# breakout.net
KiCad netlist of a schematic drawn in EAGLE
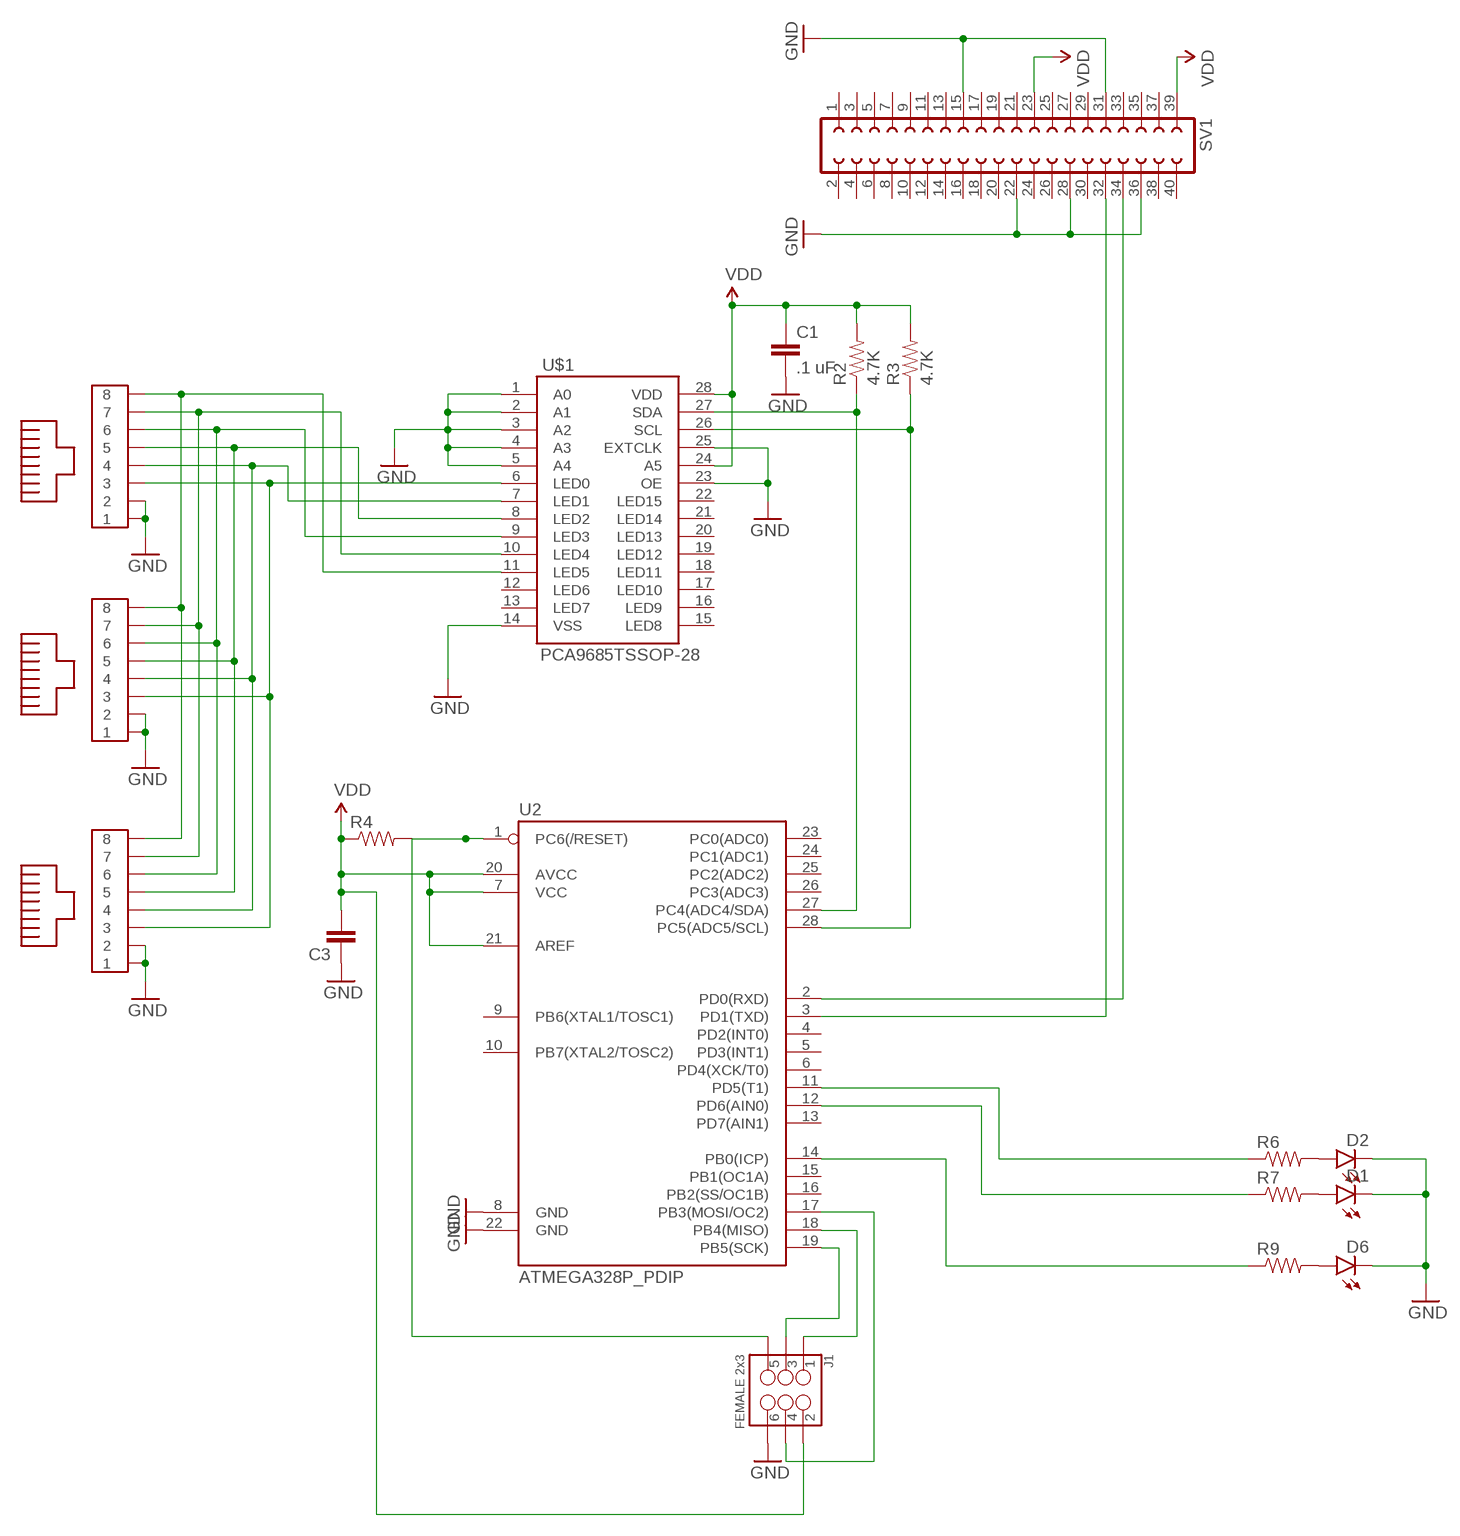
[diagram p0: schematic, sheet 1]

(export (version "E")
  (design (tool "Eeschema 10.0.6"))
  (components
    (comp (ref "C1")
      (value ".1 uF")
      (footprint "eagle-import:1206")
      (libsource (lib "eagle-import") (part "CAP1206"))
    )
    (comp (ref "C3")
      (value "CAP1206")
      (footprint "eagle-import:1206")
      (libsource (lib "eagle-import") (part "CAP1206"))
    )
    (comp (ref "D1")
      (value "LED0603")
      (footprint "eagle-import:LED-0603")
      (libsource (lib "eagle-import") (part "LED0603"))
    )
    (comp (ref "D2")
      (value "LED0603")
      (footprint "eagle-import:LED-0603")
      (libsource (lib "eagle-import") (part "LED0603"))
    )
    (comp (ref "D6")
      (value "LED0603")
      (footprint "eagle-import:LED-0603")
      (libsource (lib "eagle-import") (part "LED0603"))
    )
    (comp (ref "J1")
      (value "FEMALE 2x3")
      (footprint "eagle-import:2X3")
      (libsource (lib "eagle-import") (part "M03X2FEMALE"))
    )
    (comp (ref "R2")
      (value "4.7K")
      (footprint "eagle-import:1206")
      (libsource (lib "eagle-import") (part "RESISTOR1206"))
    )
    (comp (ref "R3")
      (value "4.7K")
      (footprint "eagle-import:1206")
      (libsource (lib "eagle-import") (part "RESISTOR1206"))
    )
    (comp (ref "R4")
      (value "RESISTOR1206")
      (footprint "eagle-import:1206")
      (libsource (lib "eagle-import") (part "RESISTOR1206"))
    )
    (comp (ref "R6")
      (value "RESISTOR1206")
      (footprint "eagle-import:1206")
      (libsource (lib "eagle-import") (part "RESISTOR1206"))
    )
    (comp (ref "R7")
      (value "RESISTOR1206")
      (footprint "eagle-import:1206")
      (libsource (lib "eagle-import") (part "RESISTOR1206"))
    )
    (comp (ref "R9")
      (value "RESISTOR1206")
      (footprint "eagle-import:1206")
      (libsource (lib "eagle-import") (part "RESISTOR1206"))
    )
    (comp (ref "SV1")
      (value "FE20-2")
      (footprint "eagle-import:FE20-2")
      (libsource (lib "eagle-import") (part "FE20-2"))
    )
    (comp (ref "U$1")
      (value "PCA9685TSSOP-28")
      (footprint "eagle-import:TSSOP28")
      (libsource (lib "eagle-import") (part "PCA9685TSSOP-28"))
    )
    (comp (ref "U$2")
      (value "MOLEX-RJ45-SMT")
      (footprint "eagle-import:MOLEX-RJ45-SMT")
      (libsource (lib "eagle-import") (part "MOLEX-RJ45-SMT"))
    )
    (comp (ref "U$3")
      (value "MOLEX-RJ45-SMT")
      (footprint "eagle-import:MOLEX-RJ45-SMT")
      (libsource (lib "eagle-import") (part "MOLEX-RJ45-SMT"))
    )
    (comp (ref "U$4")
      (value "MOLEX-RJ45-SMT")
      (footprint "eagle-import:MOLEX-RJ45-SMT")
      (libsource (lib "eagle-import") (part "MOLEX-RJ45-SMT"))
    )
    (comp (ref "U2")
      (value "ATMEGA328P_PDIP")
      (footprint "eagle-import:DIL28-3")
      (libsource (lib "eagle-import") (part "ATMEGA328P_PDIP"))
    )
  )
  (nets
    (net (code "1") (name "GND") (class "Default")
      (node (ref "C1") (pin "2") (pinfunction "2_2") (pintype "passive"))
      (node (ref "C3") (pin "1") (pinfunction "1_1") (pintype "passive"))
      (node (ref "D1") (pin "C") (pinfunction "C_C") (pintype "passive"))
      (node (ref "D2") (pin "C") (pinfunction "C_C") (pintype "passive"))
      (node (ref "D6") (pin "C") (pinfunction "C_C") (pintype "passive"))
      (node (ref "J1") (pin "6") (pinfunction "6_6") (pintype "bidirectional"))
      (node (ref "SV1") (pin "15") (pinfunction "15_15") (pintype "passive"))
      (node (ref "SV1") (pin "22") (pinfunction "22_22") (pintype "passive"))
      (node (ref "SV1") (pin "28") (pinfunction "28_28") (pintype "passive"))
      (node (ref "SV1") (pin "31") (pinfunction "31_31") (pintype "passive"))
      (node (ref "SV1") (pin "36") (pinfunction "36_36") (pintype "passive"))
      (node (ref "U$1") (pin "1") (pinfunction "A0_1") (pintype "bidirectional"))
      (node (ref "U$1") (pin "14") (pinfunction "VSS_14") (pintype "bidirectional"))
      (node (ref "U$1") (pin "2") (pinfunction "A1_2") (pintype "bidirectional"))
      (node (ref "U$1") (pin "23") (pinfunction "OE_23") (pintype "bidirectional"))
      (node (ref "U$1") (pin "25") (pinfunction "EXTCLK_25") (pintype "bidirectional"))
      (node (ref "U$1") (pin "3") (pinfunction "A2_3") (pintype "bidirectional"))
      (node (ref "U$1") (pin "4") (pinfunction "A3_4") (pintype "bidirectional"))
      (node (ref "U$1") (pin "5") (pinfunction "A4_5") (pintype "bidirectional"))
      (node (ref "U$2") (pin "1") (pinfunction "1_1") (pintype "bidirectional"))
      (node (ref "U$2") (pin "2") (pinfunction "2_2") (pintype "bidirectional"))
      (node (ref "U$3") (pin "1") (pinfunction "1_1") (pintype "bidirectional"))
      (node (ref "U$3") (pin "2") (pinfunction "2_2") (pintype "bidirectional"))
      (node (ref "U$4") (pin "1") (pinfunction "1_1") (pintype "bidirectional"))
      (node (ref "U$4") (pin "2") (pinfunction "2_2") (pintype "bidirectional"))
      (node (ref "U2") (pin "22") (pinfunction "GND_22") (pintype "bidirectional"))
      (node (ref "U2") (pin "8") (pinfunction "GND_8") (pintype "bidirectional"))
    )
    (net (code "2") (name "Net-(D1-PadA)") (class "Default")
      (node (ref "D1") (pin "A") (pinfunction "A_A") (pintype "passive"))
      (node (ref "R7") (pin "2") (pinfunction "2_2") (pintype "passive"))
    )
    (net (code "3") (name "Net-(D2-PadA)") (class "Default")
      (node (ref "D2") (pin "A") (pinfunction "A_A") (pintype "passive"))
      (node (ref "R6") (pin "2") (pinfunction "2_2") (pintype "passive"))
    )
    (net (code "4") (name "Net-(D6-PadA)") (class "Default")
      (node (ref "D6") (pin "A") (pinfunction "A_A") (pintype "passive"))
      (node (ref "R9") (pin "2") (pinfunction "2_2") (pintype "passive"))
    )
    (net (code "5") (name "Net-(U$1-LED0)") (class "Default")
      (node (ref "U$1") (pin "6") (pinfunction "LED0_6") (pintype "bidirectional"))
      (node (ref "U$2") (pin "3") (pinfunction "3_3") (pintype "bidirectional"))
      (node (ref "U$3") (pin "3") (pinfunction "3_3") (pintype "bidirectional"))
      (node (ref "U$4") (pin "3") (pinfunction "3_3") (pintype "bidirectional"))
    )
    (net (code "6") (name "Net-(U$1-LED1)") (class "Default")
      (node (ref "U$1") (pin "7") (pinfunction "LED1_7") (pintype "bidirectional"))
      (node (ref "U$2") (pin "4") (pinfunction "4_4") (pintype "bidirectional"))
      (node (ref "U$3") (pin "4") (pinfunction "4_4") (pintype "bidirectional"))
      (node (ref "U$4") (pin "4") (pinfunction "4_4") (pintype "bidirectional"))
    )
    (net (code "7") (name "Net-(U$1-LED2)") (class "Default")
      (node (ref "U$1") (pin "8") (pinfunction "LED2_8") (pintype "bidirectional"))
      (node (ref "U$2") (pin "5") (pinfunction "5_5") (pintype "bidirectional"))
      (node (ref "U$3") (pin "5") (pinfunction "5_5") (pintype "bidirectional"))
      (node (ref "U$4") (pin "5") (pinfunction "5_5") (pintype "bidirectional"))
    )
    (net (code "8") (name "Net-(U$1-LED3)") (class "Default")
      (node (ref "U$1") (pin "9") (pinfunction "LED3_9") (pintype "bidirectional"))
      (node (ref "U$2") (pin "6") (pinfunction "6_6") (pintype "bidirectional"))
      (node (ref "U$3") (pin "6") (pinfunction "6_6") (pintype "bidirectional"))
      (node (ref "U$4") (pin "6") (pinfunction "6_6") (pintype "bidirectional"))
    )
    (net (code "9") (name "Net-(U$1-LED4)") (class "Default")
      (node (ref "U$1") (pin "10") (pinfunction "LED4_10") (pintype "bidirectional"))
      (node (ref "U$2") (pin "7") (pinfunction "7_7") (pintype "bidirectional"))
      (node (ref "U$3") (pin "7") (pinfunction "7_7") (pintype "bidirectional"))
      (node (ref "U$4") (pin "7") (pinfunction "7_7") (pintype "bidirectional"))
    )
    (net (code "10") (name "Net-(U$1-LED5)") (class "Default")
      (node (ref "U$1") (pin "11") (pinfunction "LED5_11") (pintype "bidirectional"))
      (node (ref "U$2") (pin "8") (pinfunction "8_8") (pintype "bidirectional"))
      (node (ref "U$3") (pin "8") (pinfunction "8_8") (pintype "bidirectional"))
      (node (ref "U$4") (pin "8") (pinfunction "8_8") (pintype "bidirectional"))
    )
    (net (code "11") (name "Net-(U$1-SCL)") (class "Default")
      (node (ref "R3") (pin "1") (pinfunction "1_1") (pintype "passive"))
      (node (ref "U$1") (pin "26") (pinfunction "SCL_26") (pintype "bidirectional"))
      (node (ref "U2") (pin "28") (pinfunction "PC5(ADC5/SCL)_28") (pintype "bidirectional"))
    )
    (net (code "12") (name "Net-(U$1-SDA)") (class "Default")
      (node (ref "R2") (pin "1") (pinfunction "1_1") (pintype "passive"))
      (node (ref "U$1") (pin "27") (pinfunction "SDA_27") (pintype "bidirectional"))
      (node (ref "U2") (pin "27") (pinfunction "PC4(ADC4/SDA)_27") (pintype "bidirectional"))
    )
    (net (code "13") (name "Net-(U2-PB0(ICP))") (class "Default")
      (node (ref "R9") (pin "1") (pinfunction "1_1") (pintype "passive"))
      (node (ref "U2") (pin "14") (pinfunction "PB0(ICP)_14") (pintype "bidirectional"))
    )
    (net (code "14") (name "Net-(U2-PB3(MOSI{slash}OC2))") (class "Default")
      (node (ref "J1") (pin "4") (pinfunction "4_4") (pintype "bidirectional"))
      (node (ref "U2") (pin "17") (pinfunction "PB3(MOSI/OC2)_17") (pintype "bidirectional"))
    )
    (net (code "15") (name "Net-(U2-PB4(MISO))") (class "Default")
      (node (ref "J1") (pin "1") (pinfunction "1_1") (pintype "bidirectional"))
      (node (ref "U2") (pin "18") (pinfunction "PB4(MISO)_18") (pintype "bidirectional"))
    )
    (net (code "16") (name "Net-(U2-PB5(SCK))") (class "Default")
      (node (ref "J1") (pin "3") (pinfunction "3_3") (pintype "bidirectional"))
      (node (ref "U2") (pin "19") (pinfunction "PB5(SCK)_19") (pintype "bidirectional"))
    )
    (net (code "17") (name "Net-(U2-PC6({slash}RESET))") (class "Default")
      (node (ref "J1") (pin "5") (pinfunction "5_5") (pintype "bidirectional"))
      (node (ref "R4") (pin "2") (pinfunction "2_2") (pintype "passive"))
      (node (ref "U2") (pin "1") (pinfunction "PC6(/RESET)_1") (pintype "bidirectional"))
    )
    (net (code "18") (name "Net-(U2-PD0(RXD))") (class "Default")
      (node (ref "SV1") (pin "34") (pinfunction "34_34") (pintype "passive"))
      (node (ref "U2") (pin "2") (pinfunction "PD0(RXD)_2") (pintype "bidirectional"))
    )
    (net (code "19") (name "Net-(U2-PD1(TXD))") (class "Default")
      (node (ref "SV1") (pin "32") (pinfunction "32_32") (pintype "passive"))
      (node (ref "U2") (pin "3") (pinfunction "PD1(TXD)_3") (pintype "bidirectional"))
    )
    (net (code "20") (name "Net-(U2-PD5(T1))") (class "Default")
      (node (ref "R6") (pin "1") (pinfunction "1_1") (pintype "passive"))
      (node (ref "U2") (pin "11") (pinfunction "PD5(T1)_11") (pintype "bidirectional"))
    )
    (net (code "21") (name "Net-(U2-PD6(AIN0))") (class "Default")
      (node (ref "R7") (pin "1") (pinfunction "1_1") (pintype "passive"))
      (node (ref "U2") (pin "12") (pinfunction "PD6(AIN0)_12") (pintype "bidirectional"))
    )
    (net (code "22") (name "VDD") (class "Default")
      (node (ref "C1") (pin "1") (pinfunction "1_1") (pintype "passive"))
      (node (ref "C3") (pin "2") (pinfunction "2_2") (pintype "passive"))
      (node (ref "J1") (pin "2") (pinfunction "2_2") (pintype "bidirectional"))
      (node (ref "R2") (pin "2") (pinfunction "2_2") (pintype "passive"))
      (node (ref "R3") (pin "2") (pinfunction "2_2") (pintype "passive"))
      (node (ref "R4") (pin "1") (pinfunction "1_1") (pintype "passive"))
      (node (ref "SV1") (pin "23") (pinfunction "23_23") (pintype "passive"))
      (node (ref "SV1") (pin "39") (pinfunction "39_39") (pintype "passive"))
      (node (ref "U$1") (pin "24") (pinfunction "A5_24") (pintype "bidirectional"))
      (node (ref "U$1") (pin "28") (pinfunction "VDD_28") (pintype "bidirectional"))
      (node (ref "U2") (pin "20") (pinfunction "AVCC_20") (pintype "bidirectional"))
      (node (ref "U2") (pin "21") (pinfunction "AREF_21") (pintype "bidirectional"))
      (node (ref "U2") (pin "7") (pinfunction "VCC_7") (pintype "bidirectional"))
    )
    (net (code "23") (name "unconnected-(SV1-Pad1)") (class "Default")
      (node (ref "SV1") (pin "1") (pinfunction "1_1") (pintype "passive"))
    )
    (net (code "24") (name "unconnected-(SV1-Pad2)") (class "Default")
      (node (ref "SV1") (pin "2") (pinfunction "2_2") (pintype "passive"))
    )
    (net (code "25") (name "unconnected-(SV1-Pad3)") (class "Default")
      (node (ref "SV1") (pin "3") (pinfunction "3_3") (pintype "passive"))
    )
    (net (code "26") (name "unconnected-(SV1-Pad4)") (class "Default")
      (node (ref "SV1") (pin "4") (pinfunction "4_4") (pintype "passive"))
    )
    (net (code "27") (name "unconnected-(SV1-Pad5)") (class "Default")
      (node (ref "SV1") (pin "5") (pinfunction "5_5") (pintype "passive"))
    )
    (net (code "28") (name "unconnected-(SV1-Pad6)") (class "Default")
      (node (ref "SV1") (pin "6") (pinfunction "6_6") (pintype "passive"))
    )
    (net (code "29") (name "unconnected-(SV1-Pad7)") (class "Default")
      (node (ref "SV1") (pin "7") (pinfunction "7_7") (pintype "passive"))
    )
    (net (code "30") (name "unconnected-(SV1-Pad8)") (class "Default")
      (node (ref "SV1") (pin "8") (pinfunction "8_8") (pintype "passive"))
    )
    (net (code "31") (name "unconnected-(SV1-Pad9)") (class "Default")
      (node (ref "SV1") (pin "9") (pinfunction "9_9") (pintype "passive"))
    )
    (net (code "32") (name "unconnected-(SV1-Pad10)") (class "Default")
      (node (ref "SV1") (pin "10") (pinfunction "10_10") (pintype "passive"))
    )
    (net (code "33") (name "unconnected-(SV1-Pad11)") (class "Default")
      (node (ref "SV1") (pin "11") (pinfunction "11_11") (pintype "passive"))
    )
    (net (code "34") (name "unconnected-(SV1-Pad12)") (class "Default")
      (node (ref "SV1") (pin "12") (pinfunction "12_12") (pintype "passive"))
    )
    (net (code "35") (name "unconnected-(SV1-Pad13)") (class "Default")
      (node (ref "SV1") (pin "13") (pinfunction "13_13") (pintype "passive"))
    )
    (net (code "36") (name "unconnected-(SV1-Pad14)") (class "Default")
      (node (ref "SV1") (pin "14") (pinfunction "14_14") (pintype "passive"))
    )
    (net (code "37") (name "unconnected-(SV1-Pad16)") (class "Default")
      (node (ref "SV1") (pin "16") (pinfunction "16_16") (pintype "passive"))
    )
    (net (code "38") (name "unconnected-(SV1-Pad17)") (class "Default")
      (node (ref "SV1") (pin "17") (pinfunction "17_17") (pintype "passive"))
    )
    (net (code "39") (name "unconnected-(SV1-Pad18)") (class "Default")
      (node (ref "SV1") (pin "18") (pinfunction "18_18") (pintype "passive"))
    )
    (net (code "40") (name "unconnected-(SV1-Pad19)") (class "Default")
      (node (ref "SV1") (pin "19") (pinfunction "19_19") (pintype "passive"))
    )
    (net (code "41") (name "unconnected-(SV1-Pad20)") (class "Default")
      (node (ref "SV1") (pin "20") (pinfunction "20_20") (pintype "passive"))
    )
    (net (code "42") (name "unconnected-(SV1-Pad21)") (class "Default")
      (node (ref "SV1") (pin "21") (pinfunction "21_21") (pintype "passive"))
    )
    (net (code "43") (name "unconnected-(SV1-Pad24)") (class "Default")
      (node (ref "SV1") (pin "24") (pinfunction "24_24") (pintype "passive"))
    )
    (net (code "44") (name "unconnected-(SV1-Pad25)") (class "Default")
      (node (ref "SV1") (pin "25") (pinfunction "25_25") (pintype "passive"))
    )
    (net (code "45") (name "unconnected-(SV1-Pad26)") (class "Default")
      (node (ref "SV1") (pin "26") (pinfunction "26_26") (pintype "passive"))
    )
    (net (code "46") (name "unconnected-(SV1-Pad27)") (class "Default")
      (node (ref "SV1") (pin "27") (pinfunction "27_27") (pintype "passive"))
    )
    (net (code "47") (name "unconnected-(SV1-Pad29)") (class "Default")
      (node (ref "SV1") (pin "29") (pinfunction "29_29") (pintype "passive"))
    )
    (net (code "48") (name "unconnected-(SV1-Pad30)") (class "Default")
      (node (ref "SV1") (pin "30") (pinfunction "30_30") (pintype "passive"))
    )
    (net (code "49") (name "unconnected-(SV1-Pad33)") (class "Default")
      (node (ref "SV1") (pin "33") (pinfunction "33_33") (pintype "passive"))
    )
    (net (code "50") (name "unconnected-(SV1-Pad35)") (class "Default")
      (node (ref "SV1") (pin "35") (pinfunction "35_35") (pintype "passive"))
    )
    (net (code "51") (name "unconnected-(SV1-Pad37)") (class "Default")
      (node (ref "SV1") (pin "37") (pinfunction "37_37") (pintype "passive"))
    )
    (net (code "52") (name "unconnected-(SV1-Pad38)") (class "Default")
      (node (ref "SV1") (pin "38") (pinfunction "38_38") (pintype "passive"))
    )
    (net (code "53") (name "unconnected-(SV1-Pad40)") (class "Default")
      (node (ref "SV1") (pin "40") (pinfunction "40_40") (pintype "passive"))
    )
    (net (code "54") (name "unconnected-(U$1-LED6-Pad12)") (class "Default")
      (node (ref "U$1") (pin "12") (pinfunction "LED6_12") (pintype "bidirectional"))
    )
    (net (code "55") (name "unconnected-(U$1-LED7-Pad13)") (class "Default")
      (node (ref "U$1") (pin "13") (pinfunction "LED7_13") (pintype "bidirectional"))
    )
    (net (code "56") (name "unconnected-(U$1-LED8-Pad15)") (class "Default")
      (node (ref "U$1") (pin "15") (pinfunction "LED8_15") (pintype "bidirectional"))
    )
    (net (code "57") (name "unconnected-(U$1-LED9-Pad16)") (class "Default")
      (node (ref "U$1") (pin "16") (pinfunction "LED9_16") (pintype "bidirectional"))
    )
    (net (code "58") (name "unconnected-(U$1-LED10-Pad17)") (class "Default")
      (node (ref "U$1") (pin "17") (pinfunction "LED10_17") (pintype "bidirectional"))
    )
    (net (code "59") (name "unconnected-(U$1-LED11-Pad18)") (class "Default")
      (node (ref "U$1") (pin "18") (pinfunction "LED11_18") (pintype "bidirectional"))
    )
    (net (code "60") (name "unconnected-(U$1-LED12-Pad19)") (class "Default")
      (node (ref "U$1") (pin "19") (pinfunction "LED12_19") (pintype "bidirectional"))
    )
    (net (code "61") (name "unconnected-(U$1-LED13-Pad20)") (class "Default")
      (node (ref "U$1") (pin "20") (pinfunction "LED13_20") (pintype "bidirectional"))
    )
    (net (code "62") (name "unconnected-(U$1-LED14-Pad21)") (class "Default")
      (node (ref "U$1") (pin "21") (pinfunction "LED14_21") (pintype "bidirectional"))
    )
    (net (code "63") (name "unconnected-(U$1-LED15-Pad22)") (class "Default")
      (node (ref "U$1") (pin "22") (pinfunction "LED15_22") (pintype "bidirectional"))
    )
    (net (code "64") (name "unconnected-(U2-PB1(OC1A)-Pad15)") (class "Default")
      (node (ref "U2") (pin "15") (pinfunction "PB1(OC1A)_15") (pintype "bidirectional"))
    )
    (net (code "65") (name "unconnected-(U2-PB2(SS{slash}OC1B)-Pad16)") (class "Default")
      (node (ref "U2") (pin "16") (pinfunction "PB2(SS/OC1B)_16") (pintype "bidirectional"))
    )
    (net (code "66") (name "unconnected-(U2-PB6(XTAL1{slash}TOSC1)-Pad9)") (class "Default")
      (node (ref "U2") (pin "9") (pinfunction "PB6(XTAL1/TOSC1)_9") (pintype "bidirectional"))
    )
    (net (code "67") (name "unconnected-(U2-PB7(XTAL2{slash}TOSC2)-Pad10)") (class "Default")
      (node (ref "U2") (pin "10") (pinfunction "PB7(XTAL2/TOSC2)_10") (pintype "bidirectional"))
    )
    (net (code "68") (name "unconnected-(U2-PC0(ADC0)-Pad23)") (class "Default")
      (node (ref "U2") (pin "23") (pinfunction "PC0(ADC0)_23") (pintype "bidirectional"))
    )
    (net (code "69") (name "unconnected-(U2-PC1(ADC1)-Pad24)") (class "Default")
      (node (ref "U2") (pin "24") (pinfunction "PC1(ADC1)_24") (pintype "bidirectional"))
    )
    (net (code "70") (name "unconnected-(U2-PC2(ADC2)-Pad25)") (class "Default")
      (node (ref "U2") (pin "25") (pinfunction "PC2(ADC2)_25") (pintype "bidirectional"))
    )
    (net (code "71") (name "unconnected-(U2-PC3(ADC3)-Pad26)") (class "Default")
      (node (ref "U2") (pin "26") (pinfunction "PC3(ADC3)_26") (pintype "bidirectional"))
    )
    (net (code "72") (name "unconnected-(U2-PD2(INT0)-Pad4)") (class "Default")
      (node (ref "U2") (pin "4") (pinfunction "PD2(INT0)_4") (pintype "bidirectional"))
    )
    (net (code "73") (name "unconnected-(U2-PD3(INT1)-Pad5)") (class "Default")
      (node (ref "U2") (pin "5") (pinfunction "PD3(INT1)_5") (pintype "bidirectional"))
    )
    (net (code "74") (name "unconnected-(U2-PD4(XCK{slash}T0)-Pad6)") (class "Default")
      (node (ref "U2") (pin "6") (pinfunction "PD4(XCK/T0)_6") (pintype "bidirectional"))
    )
    (net (code "75") (name "unconnected-(U2-PD7(AIN1)-Pad13)") (class "Default")
      (node (ref "U2") (pin "13") (pinfunction "PD7(AIN1)_13") (pintype "bidirectional"))
    )
  )
)
